# RC_Brain_Sch.net
KiCad netlist of a schematic drawn in Altium Designer
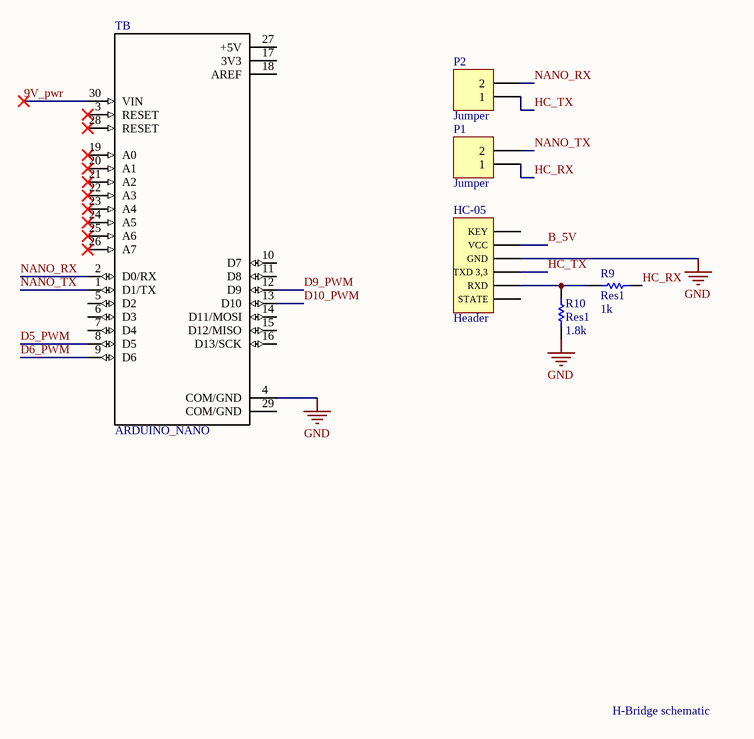
[diagram p0: RC Brain Sch.SchDoc]

(export (version "E")
  (design (tool "Eeschema 10.0.6"))
  (components
    (comp (ref "HC-05")
      (value "Header")
      (footprint "HDR1X6")
      (description "Header, 6-Pin")
      (fields (field (name "PUBLISHER") "Altium Limited"))
      (libsource (lib "Miscellaneous Connectors") (part "Header 6"))
    )
    (comp (ref "P1")
      (value "Jumper")
      (footprint "HDR1X2")
      (description "Header, 2-Pin")
      (fields (field (name "PUBLISHER") "Altium Limited"))
      (libsource (lib "Miscellaneous Connectors") (part "Header 2"))
    )
    (comp (ref "P2")
      (value "Jumper")
      (footprint "HDR1X2")
      (description "Header, 2-Pin")
      (fields (field (name "PUBLISHER") "Altium Limited"))
      (libsource (lib "Miscellaneous Connectors") (part "Header 2"))
    )
    (comp (ref "R9")
      (value "Res1")
      (footprint "6-0805_N")
      (description "Resistor")
      (fields (field (name "ALTIUM_VALUE") "1k") (field (name "PUBLISHER") "Altium Limited"))
      (libsource (lib "Miscellaneous Devices") (part "Res1"))
    )
    (comp (ref "R10")
      (value "Res1")
      (footprint "6-0805_N")
      (description "Resistor")
      (fields (field (name "ALTIUM_VALUE") "1.8k") (field (name "PUBLISHER") "Altium Limited"))
      (libsource (lib "Miscellaneous Devices") (part "Res1"))
    )
    (comp (ref "TB")
      (value "ARDUINO_NANO")
      (footprint "*SHIELD_ARDUINO_NANO")
      (description "ATmega328 Arduino Nano AVRÂ® ATmega AVR MCU 8-Bit Embedded Evaluation Board")
      (fields (field (name "MF") "Arduino") (field (name "MP") "ARDUINO NANO"))
      (libsource (lib "ARDUINO_NANO") (part "ARDUINO_NANO"))
    )
  )
  (nets
    (net (code "1") (name "/9V_pwr") (class "Default")
      (node (ref "TB") (pin "30") (pinfunction "VIN_30") (pintype "input+no_connect"))
    )
    (net (code "2") (name "/B_5V") (class "Default")
      (node (ref "HC-05") (pin "2") (pinfunction "VCC_2") (pintype "passive"))
    )
    (net (code "3") (name "/D5_PWM") (class "Default")
      (node (ref "TB") (pin "8") (pinfunction "D5_8") (pintype "bidirectional"))
    )
    (net (code "4") (name "/D6_PWM") (class "Default")
      (node (ref "TB") (pin "9") (pinfunction "D6_9") (pintype "bidirectional"))
    )
    (net (code "5") (name "/D9_PWM") (class "Default")
      (node (ref "TB") (pin "12") (pinfunction "D9_12") (pintype "bidirectional"))
    )
    (net (code "6") (name "/D10_PWM") (class "Default")
      (node (ref "TB") (pin "13") (pinfunction "D10_13") (pintype "bidirectional"))
    )
    (net (code "7") (name "/HC_RX") (class "Default")
      (node (ref "P1") (pin "1") (pinfunction "1_1") (pintype "passive"))
      (node (ref "R9") (pin "2") (pinfunction "2_2") (pintype "passive"))
    )
    (net (code "8") (name "/HC_TX") (class "Default")
      (node (ref "HC-05") (pin "4") (pinfunction "TXD_3,3_4") (pintype "passive"))
      (node (ref "P2") (pin "1") (pinfunction "1_1") (pintype "passive"))
    )
    (net (code "9") (name "/NANO_RX") (class "Default")
      (node (ref "P2") (pin "2") (pinfunction "2_2") (pintype "passive"))
      (node (ref "TB") (pin "2") (pinfunction "D0/RX_2") (pintype "bidirectional"))
    )
    (net (code "10") (name "/NANO_TX") (class "Default")
      (node (ref "P1") (pin "2") (pinfunction "2_2") (pintype "passive"))
      (node (ref "TB") (pin "1") (pinfunction "D1/TX_1") (pintype "bidirectional"))
    )
    (net (code "11") (name "GND") (class "Default")
      (node (ref "HC-05") (pin "3") (pinfunction "GND_3") (pintype "passive"))
      (node (ref "R10") (pin "1") (pinfunction "1_1") (pintype "passive"))
      (node (ref "TB") (pin "4") (pinfunction "COM/GND_4") (pintype "power_in"))
    )
    (net (code "12") (name "Net-(HC-05-RXD)") (class "Default")
      (node (ref "HC-05") (pin "5") (pinfunction "RXD_5") (pintype "passive"))
      (node (ref "R10") (pin "2") (pinfunction "2_2") (pintype "passive"))
      (node (ref "R9") (pin "1") (pinfunction "1_1") (pintype "passive"))
    )
    (net (code "13") (name "unconnected-(HC-05-KEY-Pad1)") (class "Default")
      (node (ref "HC-05") (pin "1") (pinfunction "KEY_1") (pintype "passive"))
    )
    (net (code "14") (name "unconnected-(HC-05-STATE-Pad6)") (class "Default")
      (node (ref "HC-05") (pin "6") (pinfunction "STATE_6") (pintype "passive"))
    )
    (net (code "15") (name "unconnected-(TB-+5V-Pad27)") (class "Default")
      (node (ref "TB") (pin "27") (pinfunction "+5V_27") (pintype "power_in"))
    )
    (net (code "16") (name "unconnected-(TB-3V3-Pad17)") (class "Default")
      (node (ref "TB") (pin "17") (pinfunction "3V3_17") (pintype "power_in"))
    )
    (net (code "17") (name "unconnected-(TB-A0-Pad19)") (class "Default")
      (node (ref "TB") (pin "19") (pinfunction "A0_19") (pintype "input+no_connect"))
    )
    (net (code "18") (name "unconnected-(TB-A1-Pad20)") (class "Default")
      (node (ref "TB") (pin "20") (pinfunction "A1_20") (pintype "input+no_connect"))
    )
    (net (code "19") (name "unconnected-(TB-A2-Pad21)") (class "Default")
      (node (ref "TB") (pin "21") (pinfunction "A2_21") (pintype "input+no_connect"))
    )
    (net (code "20") (name "unconnected-(TB-A3-Pad22)") (class "Default")
      (node (ref "TB") (pin "22") (pinfunction "A3_22") (pintype "input+no_connect"))
    )
    (net (code "21") (name "unconnected-(TB-A4-Pad23)") (class "Default")
      (node (ref "TB") (pin "23") (pinfunction "A4_23") (pintype "input+no_connect"))
    )
    (net (code "22") (name "unconnected-(TB-A5-Pad24)") (class "Default")
      (node (ref "TB") (pin "24") (pinfunction "A5_24") (pintype "input+no_connect"))
    )
    (net (code "23") (name "unconnected-(TB-A6-Pad25)") (class "Default")
      (node (ref "TB") (pin "25") (pinfunction "A6_25") (pintype "input+no_connect"))
    )
    (net (code "24") (name "unconnected-(TB-A7-Pad26)") (class "Default")
      (node (ref "TB") (pin "26") (pinfunction "A7_26") (pintype "input+no_connect"))
    )
    (net (code "25") (name "unconnected-(TB-AREF-Pad18)") (class "Default")
      (node (ref "TB") (pin "18") (pinfunction "AREF_18") (pintype "power_in"))
    )
    (net (code "26") (name "unconnected-(TB-COM{slash}GND-Pad29)") (class "Default")
      (node (ref "TB") (pin "29") (pinfunction "COM/GND_29") (pintype "power_in"))
    )
    (net (code "27") (name "unconnected-(TB-D2-Pad5)") (class "Default")
      (node (ref "TB") (pin "5") (pinfunction "D2_5") (pintype "bidirectional"))
    )
    (net (code "28") (name "unconnected-(TB-D3-Pad6)") (class "Default")
      (node (ref "TB") (pin "6") (pinfunction "D3_6") (pintype "bidirectional"))
    )
    (net (code "29") (name "unconnected-(TB-D4-Pad7)") (class "Default")
      (node (ref "TB") (pin "7") (pinfunction "D4_7") (pintype "bidirectional"))
    )
    (net (code "30") (name "unconnected-(TB-D7-Pad10)") (class "Default")
      (node (ref "TB") (pin "10") (pinfunction "D7_10") (pintype "bidirectional"))
    )
    (net (code "31") (name "unconnected-(TB-D8-Pad11)") (class "Default")
      (node (ref "TB") (pin "11") (pinfunction "D8_11") (pintype "bidirectional"))
    )
    (net (code "32") (name "unconnected-(TB-D11{slash}MOSI-Pad14)") (class "Default")
      (node (ref "TB") (pin "14") (pinfunction "D11/MOSI_14") (pintype "bidirectional"))
    )
    (net (code "33") (name "unconnected-(TB-D12{slash}MISO-Pad15)") (class "Default")
      (node (ref "TB") (pin "15") (pinfunction "D12/MISO_15") (pintype "bidirectional"))
    )
    (net (code "34") (name "unconnected-(TB-D13{slash}SCK-Pad16)") (class "Default")
      (node (ref "TB") (pin "16") (pinfunction "D13/SCK_16") (pintype "bidirectional"))
    )
    (net (code "35") (name "unconnected-(TB-RESET-Pad3)") (class "Default")
      (node (ref "TB") (pin "3") (pinfunction "RESET_3") (pintype "input+no_connect"))
    )
    (net (code "36") (name "unconnected-(TB-RESET-Pad28)") (class "Default")
      (node (ref "TB") (pin "28") (pinfunction "RESET_28") (pintype "input+no_connect"))
    )
  )
)
